# Programmer.net
KiCad netlist of a schematic drawn in Altium Designer
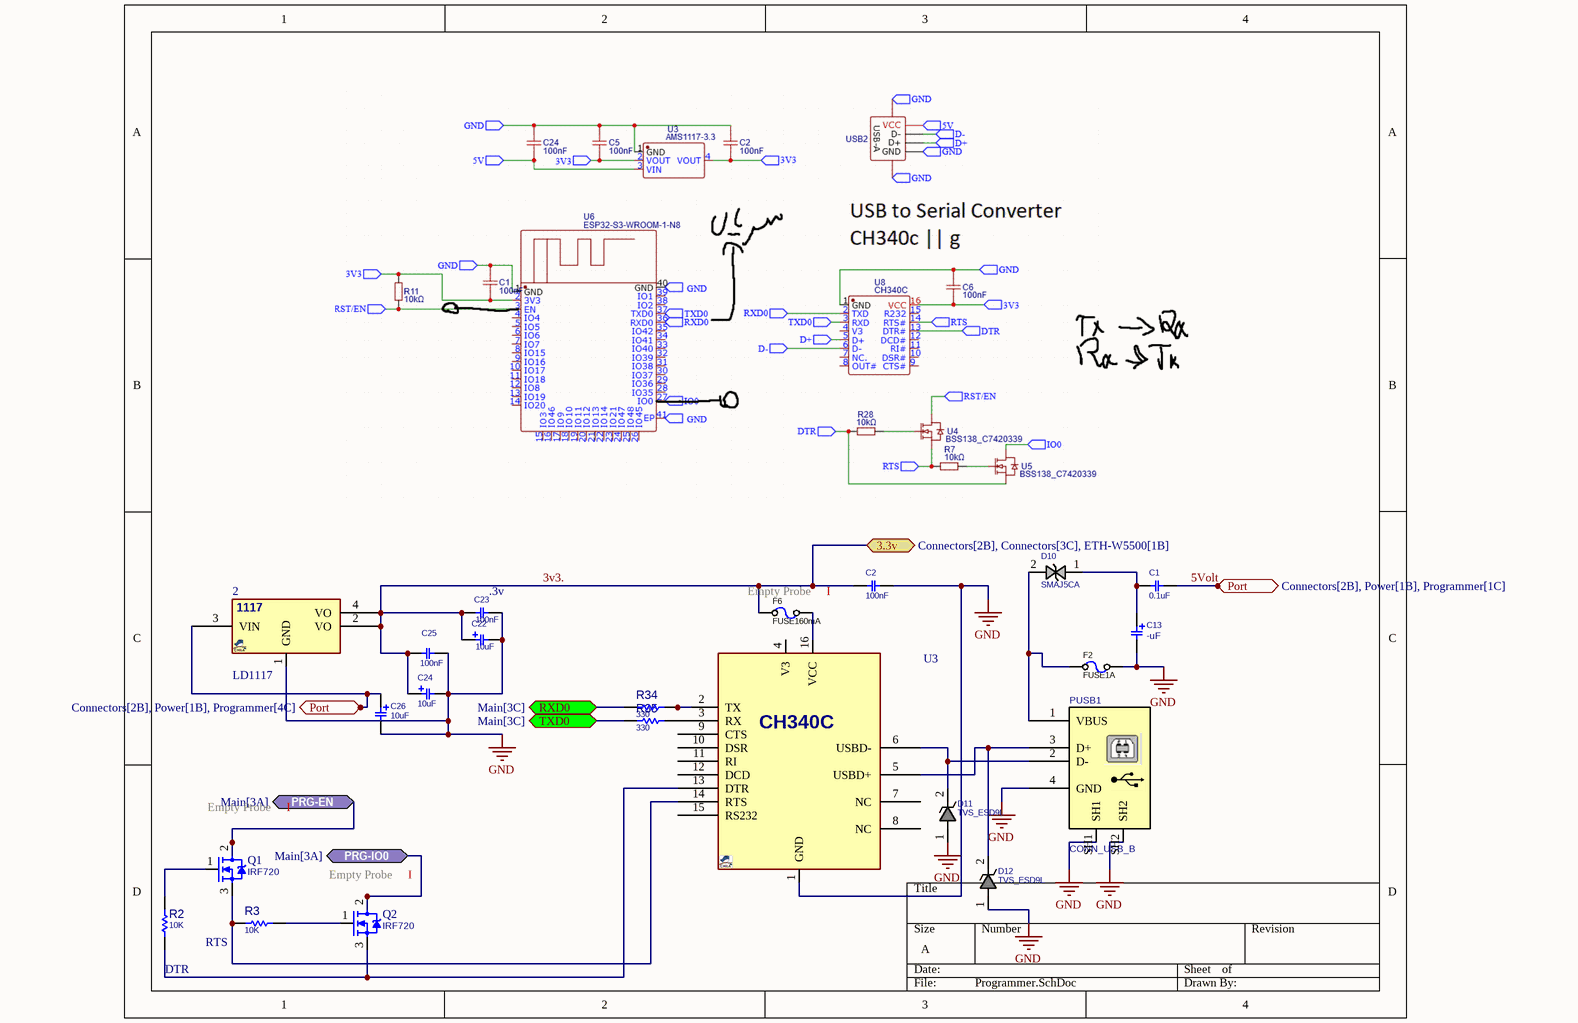
[diagram p0: Programmer.SchDoc]

(export (version "E")
  (design (tool "Eeschema 10.0.6"))
  (components
    (comp (ref "2")
      (value "LD1117")
      (footprint "SOT223_4")
      (description "REG, Linear, LDO1V, 0.8A, SOT-223")
      (fields
        (field (name "MANF_P#") "LD1117, LM1117, AMS1117, TLV1117, REG1117, NCP1117, LT1117, SPX1117")
        (field (name "MANF") "TI, ON, ST")
      )
      (libsource (lib "pwr_reg_linear_1117") (part "VREG_1117_SOT223"))
    )
    (comp (ref "C1")
      (value "0.1uF")
      (footprint "C_CERM_D4")
      (description "CAP, THD, CER MULTI LAYER,")
      (fields (field (name "MANF_P#") "MANF_PART#") (field (name "MANF") "MANF"))
      (libsource (lib "passive_thd") (part "CAP_THD_CER_0.1uF_50v"))
    )
    (comp (ref "C2")
      (value "100nF")
      (footprint "C_CERM_D3")
      (description "CAP, THD, CER MULTI LAYER,")
      (fields (field (name "MANF_P#") "MANF_PART#") (field (name "MANF") "MANF"))
      (libsource (lib "passive_thd") (part "CAP_THD_CER"))
    )
    (comp (ref "C13")
      (value "-uF")
      (footprint "C_TN_3216")
      (description "CAP, SMD, TAN,")
      (libsource (lib "passive_smd") (part "CAP_SMD_TAN_3216"))
    )
    (comp (ref "C22")
      (value "10uF")
      (footprint "C_EL_4X7")
      (description "CAP, THD, ELEC, 10uF, 25V")
      (fields (field (name "MANF") "MANF") (field (name "MANF_P#") "MANF_PART#"))
      (libsource (lib "passive_thd") (part "CAP_THD_EL_10u25V"))
    )
    (comp (ref "C23")
      (value "100nF")
      (footprint "C_CERM_D3")
      (description "CAP, THD, CER MULTI LAYER,")
      (fields (field (name "MANF_P#") "MANF_PART#") (field (name "MANF") "MANF"))
      (libsource (lib "passive_thd") (part "CAP_THD_CER"))
    )
    (comp (ref "C24")
      (value "10uF")
      (footprint "C_EL_4X7")
      (description "CAP, THD, ELEC, 10uF, 25V")
      (fields (field (name "MANF") "MANF") (field (name "MANF_P#") "MANF_PART#"))
      (libsource (lib "passive_thd") (part "CAP_THD_EL_10u25V"))
    )
    (comp (ref "C25")
      (value "100nF")
      (footprint "C_CERM_D3")
      (description "CAP, THD, CER MULTI LAYER,")
      (fields (field (name "MANF_P#") "MANF_PART#") (field (name "MANF") "MANF"))
      (libsource (lib "passive_thd") (part "CAP_THD_CER"))
    )
    (comp (ref "C26")
      (value "10uF")
      (footprint "C_EL_4X7")
      (description "CAP, THD, ELEC, 10uF, 25V")
      (fields (field (name "MANF") "MANF") (field (name "MANF_P#") "MANF_PART#"))
      (libsource (lib "passive_thd") (part "CAP_THD_EL_10u25V"))
    )
    (comp (ref "D10")
      (value "SMAJ5CA")
      (footprint "D_SMA")
      (description "TVS, ESD PROTECT, Bidirectional")
      (fields (field (name "MANF") "Littelfuse"))
      (libsource (lib "protect_tvs_esd_fuse") (part "TVS_SMAJ5CA"))
    )
    (comp (ref "D11")
      (value "TVS_ESD9L")
      (footprint "D_SOD923")
      (description "TVS, ESD PROTECT,")
      (fields (field (name "MANF_P#") "ESD9L5.0ST5G") (field (name "MANF") "ON"))
      (libsource (lib "protect_tvs_esd_fuse") (part "TVS_ESD9L5"))
    )
    (comp (ref "D12")
      (value "TVS_ESD9L")
      (footprint "D_SOD923")
      (description "TVS, ESD PROTECT,")
      (fields (field (name "MANF_P#") "ESD9L5.0ST5G") (field (name "MANF") "ON"))
      (libsource (lib "protect_tvs_esd_fuse") (part "TVS_ESD9L5"))
    )
    (comp (ref "F2")
      (value "FUSE1A")
      (footprint "F2920")
      (description "Fuse, PPTC, 1A, 60v, 410mOhm, 2920")
      (fields (field (name "MANF") "Bel Fuse") (field (name "MANF_P#") "0ZCF0100AF2A"))
      (libsource (lib "protect_tvs_esd_fuse") (part "FUSE_PPTC1A_2920"))
    )
    (comp (ref "F6")
      (value "FUSE160mA")
      (footprint "F1206")
      (description "Fuse, 160mA, 63VDC, 1206, SMD, Fast Acting")
      (fields (field (name "MANF") "Holly Fuse") (field (name "MANF_P#") "12T-0160L"))
      (libsource (lib "protect_tvs_esd_fuse") (part "FUSE_160mA_1206"))
    )
    (comp (ref "PUSB1")
      (value "CONN_USB_B")
      (footprint "USB_B_RA_THD")
      (description "CONN, USB, B, R/A, THD")
      (fields (field (name "MANF_P#") "292304-1") (field (name "MANF") "TE Connectivity"))
      (libsource (lib "conn_usb") (part "CONN_USB_B_RA_THD"))
    )
    (comp (ref "Q1")
      (value "IRF720")
      (footprint "TO220_3")
      (description "MOSFET, N-CH, 1.8RDS, 3.3A, 400VDS, 2~4VGSth")
      (fields (field (name "MANF") "VISHAY, ON"))
      (libsource (lib "transistor_fet") (part "MOSN_IRF720_TO220"))
    )
    (comp (ref "Q2")
      (value "IRF720")
      (footprint "TO220_3")
      (description "MOSFET, N-CH, 1.8RDS, 3.3A, 400VDS, 2~4VGSth")
      (fields (field (name "MANF") "VISHAY, ON"))
      (libsource (lib "transistor_fet") (part "MOSN_IRF720_TO220"))
    )
    (comp (ref "R2")
      (value "10K")
      (footprint "R025W_AX04")
      (description "RESISTOR, THD")
      (fields (field (name "MANF_P#") "RK73H1ETTP4701F") (field (name "MANF") "KOA SPEER"))
      (libsource (lib "passive_thd") (part "RES_THD"))
    )
    (comp (ref "R3")
      (value "10K")
      (footprint "R025W_AX04")
      (description "RESISTOR, THD")
      (fields (field (name "MANF_P#") "RK73H1ETTP4701F") (field (name "MANF") "KOA SPEER"))
      (libsource (lib "passive_thd") (part "RES_THD"))
    )
    (comp (ref "R34")
      (value "330")
      (footprint "R025W_AX04")
      (description "RESISTOR, THD")
      (fields (field (name "MANF_P#") "RK73H1ETTP4701F") (field (name "MANF") "KOA SPEER"))
      (libsource (lib "passive_thd") (part "RES_THD"))
    )
    (comp (ref "R35")
      (value "330")
      (footprint "R025W_AX04")
      (description "RESISTOR, THD")
      (fields (field (name "MANF_P#") "RK73H1ETTP4701F") (field (name "MANF") "KOA SPEER"))
      (libsource (lib "passive_thd") (part "RES_THD"))
    )
    (comp (ref "U3")
      (value "CH340C")
      (footprint "SO_16")
      (description "USB-UART")
      (libsource (lib "usbic") (part "CH340C_SOP16"))
    )
  )
  (nets
    (net (code "1") (name "/3v3.") (class "Default")
      (node (ref "2") (pin "2") (pinfunction "VO_2") (pintype "passive"))
      (node (ref "2") (pin "4") (pinfunction "VO_4") (pintype "passive"))
      (node (ref "C2") (pin "2") (pinfunction "2_2") (pintype "passive"))
      (node (ref "C22") (pin "1") (pinfunction "1_1") (pintype "passive"))
      (node (ref "C23") (pin "1") (pinfunction "1_1") (pintype "passive"))
      (node (ref "C24") (pin "1") (pinfunction "1_1") (pintype "passive"))
      (node (ref "C25") (pin "1") (pinfunction "1_1") (pintype "passive"))
      (node (ref "F6") (pin "1") (pinfunction "1_1") (pintype "passive"))
    )
    (net (code "2") (name "/5Volt") (class "Default")
      (node (ref "2") (pin "3") (pinfunction "VIN_3") (pintype "passive"))
      (node (ref "C1") (pin "2") (pinfunction "2_2") (pintype "passive"))
      (node (ref "C26") (pin "1") (pinfunction "1_1") (pintype "passive"))
    )
    (net (code "3") (name "/PRG-EN") (class "Default")
      (node (ref "Q1") (pin "2") (pinfunction "D_2") (pintype "passive"))
    )
    (net (code "4") (name "/PRG-IO0") (class "Default")
      (node (ref "Q2") (pin "2") (pinfunction "D_2") (pintype "passive"))
    )
    (net (code "5") (name "/RXD0") (class "Default")
      (node (ref "R34") (pin "1") (pinfunction "1_1") (pintype "passive"))
    )
    (net (code "6") (name "/TXD0") (class "Default")
      (node (ref "R35") (pin "1") (pinfunction "1_1") (pintype "passive"))
    )
    (net (code "7") (name "GND") (class "Default")
      (node (ref "2") (pin "1") (pinfunction "GND_1") (pintype "passive"))
      (node (ref "C13") (pin "2") (pinfunction "2_2") (pintype "passive"))
      (node (ref "C2") (pin "1") (pinfunction "1_1") (pintype "passive"))
      (node (ref "C22") (pin "2") (pinfunction "2_2") (pintype "passive"))
      (node (ref "C23") (pin "2") (pinfunction "2_2") (pintype "passive"))
      (node (ref "C24") (pin "2") (pinfunction "2_2") (pintype "passive"))
      (node (ref "C25") (pin "2") (pinfunction "2_2") (pintype "passive"))
      (node (ref "C26") (pin "2") (pinfunction "2_2") (pintype "passive"))
      (node (ref "D11") (pin "1") (pinfunction "1_1") (pintype "passive"))
      (node (ref "D12") (pin "1") (pinfunction "1_1") (pintype "passive"))
      (node (ref "F2") (pin "1") (pinfunction "1_1") (pintype "passive"))
      (node (ref "PUSB1") (pin "4") (pinfunction "GND_4") (pintype "power_in"))
      (node (ref "PUSB1") (pin "SH1") (pinfunction "SH1_SH1") (pintype "passive"))
      (node (ref "PUSB1") (pin "SH2") (pinfunction "SH2_SH2") (pintype "passive"))
      (node (ref "U3") (pin "1") (pinfunction "GND_1") (pintype "passive"))
    )
    (net (code "8") (name "Net-(C1-Pad1)") (class "Default")
      (node (ref "C1") (pin "1") (pinfunction "1_1") (pintype "passive"))
      (node (ref "C13") (pin "1") (pinfunction "1_1") (pintype "passive"))
      (node (ref "D10") (pin "1") (pinfunction "1_1") (pintype "passive"))
    )
    (net (code "9") (name "Net-(PUSB1-D+)") (class "Default")
      (node (ref "D12") (pin "2") (pinfunction "2_2") (pintype "passive"))
      (node (ref "PUSB1") (pin "3") (pinfunction "D+_3") (pintype "passive"))
      (node (ref "U3") (pin "5") (pinfunction "USBD+_5") (pintype "passive"))
    )
    (net (code "10") (name "Net-(PUSB1-D-)") (class "Default")
      (node (ref "D11") (pin "2") (pinfunction "2_2") (pintype "passive"))
      (node (ref "PUSB1") (pin "2") (pinfunction "D-_2") (pintype "passive"))
      (node (ref "U3") (pin "6") (pinfunction "USBD-_6") (pintype "passive"))
    )
    (net (code "11") (name "Net-(PUSB1-VBUS)") (class "Default")
      (node (ref "D10") (pin "2") (pinfunction "2_2") (pintype "passive"))
      (node (ref "F2") (pin "2") (pinfunction "2_2") (pintype "passive"))
      (node (ref "PUSB1") (pin "1") (pinfunction "VBUS_1") (pintype "power_in"))
    )
    (net (code "12") (name "Net-(Q1-G)") (class "Default")
      (node (ref "Q1") (pin "1") (pinfunction "G_1") (pintype "passive"))
      (node (ref "R2") (pin "2") (pinfunction "2_2") (pintype "passive"))
    )
    (net (code "13") (name "Net-(Q1-S)") (class "Default")
      (node (ref "Q1") (pin "3") (pinfunction "S_3") (pintype "passive"))
      (node (ref "R3") (pin "1") (pinfunction "1_1") (pintype "passive"))
      (node (ref "U3") (pin "14") (pinfunction "RTS_14") (pintype "passive"))
    )
    (net (code "14") (name "Net-(Q2-G)") (class "Default")
      (node (ref "Q2") (pin "1") (pinfunction "G_1") (pintype "passive"))
      (node (ref "R3") (pin "2") (pinfunction "2_2") (pintype "passive"))
    )
    (net (code "15") (name "Net-(Q2-S)") (class "Default")
      (node (ref "Q2") (pin "3") (pinfunction "S_3") (pintype "passive"))
      (node (ref "R2") (pin "1") (pinfunction "1_1") (pintype "passive"))
      (node (ref "U3") (pin "13") (pinfunction "DTR_13") (pintype "passive"))
    )
    (net (code "16") (name "Net-(U3-RX)") (class "Default")
      (node (ref "R35") (pin "2") (pinfunction "2_2") (pintype "passive"))
      (node (ref "U3") (pin "3") (pinfunction "RX_3") (pintype "passive"))
    )
    (net (code "17") (name "Net-(U3-TX)") (class "Default")
      (node (ref "R34") (pin "2") (pinfunction "2_2") (pintype "passive"))
      (node (ref "U3") (pin "2") (pinfunction "TX_2") (pintype "passive"))
    )
    (net (code "18") (name "Net-(U3-VCC)") (class "Default")
      (node (ref "F6") (pin "2") (pinfunction "2_2") (pintype "passive"))
      (node (ref "U3") (pin "16") (pinfunction "VCC_16") (pintype "passive"))
    )
    (net (code "19") (name "unconnected-(U3-CTS-Pad9)") (class "Default")
      (node (ref "U3") (pin "9") (pinfunction "CTS_9") (pintype "passive"))
    )
    (net (code "20") (name "unconnected-(U3-DCD-Pad12)") (class "Default")
      (node (ref "U3") (pin "12") (pinfunction "DCD_12") (pintype "passive"))
    )
    (net (code "21") (name "unconnected-(U3-DSR-Pad10)") (class "Default")
      (node (ref "U3") (pin "10") (pinfunction "DSR_10") (pintype "passive"))
    )
    (net (code "22") (name "unconnected-(U3-NC-Pad7)") (class "Default")
      (node (ref "U3") (pin "7") (pinfunction "NC_7") (pintype "passive"))
    )
    (net (code "23") (name "unconnected-(U3-NC-Pad8)") (class "Default")
      (node (ref "U3") (pin "8") (pinfunction "NC_8") (pintype "passive"))
    )
    (net (code "24") (name "unconnected-(U3-RI-Pad11)") (class "Default")
      (node (ref "U3") (pin "11") (pinfunction "RI_11") (pintype "passive"))
    )
    (net (code "25") (name "unconnected-(U3-RS232-Pad15)") (class "Default")
      (node (ref "U3") (pin "15") (pinfunction "RS232_15") (pintype "passive"))
    )
    (net (code "26") (name "unconnected-(U3-V3-Pad4)") (class "Default")
      (node (ref "U3") (pin "4") (pinfunction "V3_4") (pintype "passive"))
    )
  )
)
